# Mechanical.net
KiCad netlist of a schematic drawn in Altium Designer
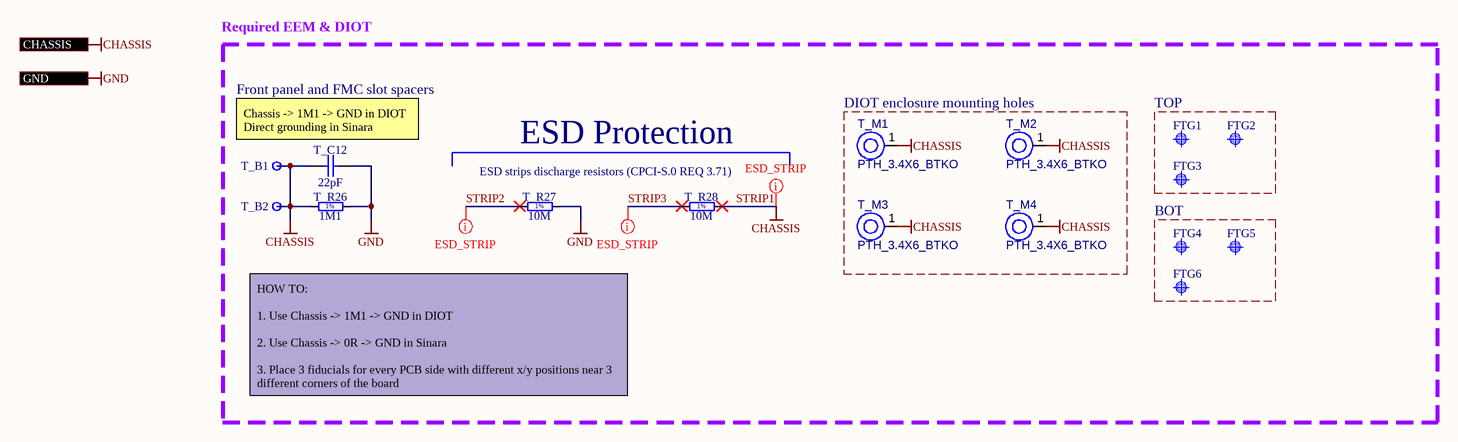
[diagram p0: Mechanical.SchDoc]

(export (version "E")
  (design (tool "Eeschema 10.0.6"))
  (components
    (comp (ref "FTG1")
      (value "Use only in PCB")
      (footprint "FIDUCIAL_TOP_C100-200")
      (description "Fiducial Target")
      (fields (field (name "PART NUMBER") "FIDUCIAL_TARGET_C100-200") (field (name "AUTHOR") "CERN DEM JLC"))
      (libsource (lib "Eletro-mechanical") (part "Fiducial Target"))
    )
    (comp (ref "FTG2")
      (value "Use only in PCB")
      (footprint "FIDUCIAL_TOP_S100-200")
      (description "Fiducial Target")
      (fields (field (name "PART NUMBER") "FIDUCIAL_TARGET_S100-200") (field (name "AUTHOR") "CERN DEM JLC"))
      (libsource (lib "Eletro-mechanical") (part "Fiducial Target"))
    )
    (comp (ref "FTG3")
      (value "Use only in PCB")
      (footprint "FIDUCIAL_TOP_S100-200")
      (description "Fiducial Target")
      (fields (field (name "PART NUMBER") "FIDUCIAL_TARGET_S100-200") (field (name "AUTHOR") "CERN DEM JLC"))
      (libsource (lib "Eletro-mechanical") (part "Fiducial Target"))
    )
    (comp (ref "FTG4")
      (value "Use only in PCB")
      (footprint "FIDUCIAL_TOP_C100-200")
      (description "Fiducial Target")
      (fields (field (name "PART NUMBER") "FIDUCIAL_TARGET_C100-200") (field (name "AUTHOR") "CERN DEM JLC"))
      (libsource (lib "Eletro-mechanical") (part "Fiducial Target"))
    )
    (comp (ref "FTG5")
      (value "Use only in PCB")
      (footprint "FIDUCIAL_TOP_S100-200")
      (description "Fiducial Target")
      (fields (field (name "PART NUMBER") "FIDUCIAL_TARGET_S100-200") (field (name "AUTHOR") "CERN DEM JLC"))
      (libsource (lib "Eletro-mechanical") (part "Fiducial Target"))
    )
    (comp (ref "FTG6")
      (value "Use only in PCB")
      (footprint "FIDUCIAL_TOP_S100-200")
      (description "Fiducial Target")
      (fields (field (name "PART NUMBER") "FIDUCIAL_TARGET_S100-200") (field (name "AUTHOR") "CERN DEM JLC"))
      (libsource (lib "Eletro-mechanical") (part "Fiducial Target"))
    )
    (comp (ref "T_B1")
      (value "Plated Hole")
      (footprint "c600h270")
      (description "Single Terminal Socket")
      (fields (field (name "PART NUMBER") "PLATED_HOLE2.7_PAD6.0") (field (name "AUTHOR") "CERN DEM HF"))
      (libsource (lib "Eletro-mechanical") (part "Single Terminal Socket"))
    )
    (comp (ref "T_B2")
      (value "Plated Hole")
      (footprint "c600h270")
      (description "Single Terminal Socket")
      (fields (field (name "PART NUMBER") "PLATED_HOLE2.7_PAD6.0") (field (name "AUTHOR") "CERN DEM HF"))
      (libsource (lib "Eletro-mechanical") (part "Single Terminal Socket"))
    )
    (comp (ref "T_C12")
      (value "22pF")
      (footprint "CAPC1005X55N")
      (description "Non-polarised capacitor")
      (fields
        (field (name "PART NUMBER") "CC0402_22PF_50V_5%_C0G")
        (field (name "VOLTAGE") "50V")
        (field (name "AUTHOR") "CERN DEM JLC")
      )
      (libsource (lib "Capacitors") (part "Capacitor - non polarized"))
    )
    (comp (ref "T_M1")
      (value "PTH_3.4X6_BTKO")
      (footprint "PTH-M3.4x6.0_BTKO")
      (description "PTH  Hole 3.4, 6mm pad")
      (libsource (lib "TechnoSystem Workspace") (part "PTH3.4x6.0_BTKO"))
    )
    (comp (ref "T_M2")
      (value "PTH_3.4X6_BTKO")
      (footprint "PTH-M3.4x6.0_BTKO")
      (description "PTH  Hole 3.4, 6mm pad")
      (libsource (lib "TechnoSystem Workspace") (part "PTH3.4x6.0_BTKO"))
    )
    (comp (ref "T_M3")
      (value "PTH_3.4X6_BTKO")
      (footprint "PTH-M3.4x6.0_BTKO")
      (description "PTH  Hole 3.4, 6mm pad")
      (libsource (lib "TechnoSystem Workspace") (part "PTH3.4x6.0_BTKO"))
    )
    (comp (ref "T_M4")
      (value "PTH_3.4X6_BTKO")
      (footprint "PTH-M3.4x6.0_BTKO")
      (description "PTH  Hole 3.4, 6mm pad")
      (libsource (lib "TechnoSystem Workspace") (part "PTH3.4x6.0_BTKO"))
    )
    (comp (ref "T_R26")
      (value "1M1")
      (footprint "RESC2012X60N")
      (description "Resistor - 1%")
      (fields
        (field (name "PART NUMBER") "R0805_1M1_1%_0.125W_100PPM")
        (field (name "MANUFACTURER") "GENERIC")
        (field (name "AUTHOR") "CERN DEM JLC")
      )
      (libsource (lib "Resistors") (part "Resistor - 1%"))
    )
    (comp (ref "T_R27")
      (value "10M")
      (footprint "RESC2113X55N")
      (description "Resistor - 1%")
      (fields
        (field (name "PART NUMBER") "R0805_10M_1%_0.125W_100PPM_VISHAY_CRCW e3")
        (field (name "POWER") "0.125W")
        (field (name "AUTHOR") "CERN DEM BC")
      )
      (libsource (lib "Resistors") (part "Resistor - 1%"))
    )
    (comp (ref "T_R28")
      (value "10M")
      (footprint "RESC2113X55N")
      (description "Resistor - 1%")
      (fields
        (field (name "PART NUMBER") "R0805_10M_1%_0.125W_100PPM_VISHAY_CRCW e3")
        (field (name "POWER") "0.125W")
        (field (name "AUTHOR") "CERN DEM BC")
      )
      (libsource (lib "Resistors") (part "Resistor - 1%"))
    )
  )
  (nets
    (net (code "1") (name "/STRIP2") (class "Default")
      (node (ref "T_R27") (pin "1") (pinfunction "1_1") (pintype "passive+no_connect"))
    )
    (net (code "2") (name "/STRIP3") (class "Default")
      (node (ref "T_R28") (pin "1") (pinfunction "1_1") (pintype "passive+no_connect"))
    )
    (net (code "3") (name "CHASSIS") (class "Default")
      (node (ref "T_B1") (pin "1") (pinfunction "1_1") (pintype "bidirectional"))
      (node (ref "T_B2") (pin "1") (pinfunction "1_1") (pintype "bidirectional"))
      (node (ref "T_C12") (pin "1") (pinfunction "1_1") (pintype "passive"))
      (node (ref "T_M1") (pin "1") (pinfunction "H1_1") (pintype "passive"))
      (node (ref "T_M2") (pin "1") (pinfunction "H1_1") (pintype "passive"))
      (node (ref "T_M3") (pin "1") (pinfunction "H1_1") (pintype "passive"))
      (node (ref "T_M4") (pin "1") (pinfunction "H1_1") (pintype "passive"))
      (node (ref "T_R26") (pin "1") (pinfunction "1_1") (pintype "passive"))
      (node (ref "T_R28") (pin "2") (pinfunction "2_2") (pintype "passive"))
    )
    (net (code "4") (name "GND") (class "Default")
      (node (ref "T_C12") (pin "2") (pinfunction "2_2") (pintype "passive"))
      (node (ref "T_R26") (pin "2") (pinfunction "2_2") (pintype "passive"))
      (node (ref "T_R27") (pin "2") (pinfunction "2_2") (pintype "passive"))
    )
  )
)
